# Senslope_Alpha_4_8.net
KiCad netlist of a schematic drawn in EAGLE
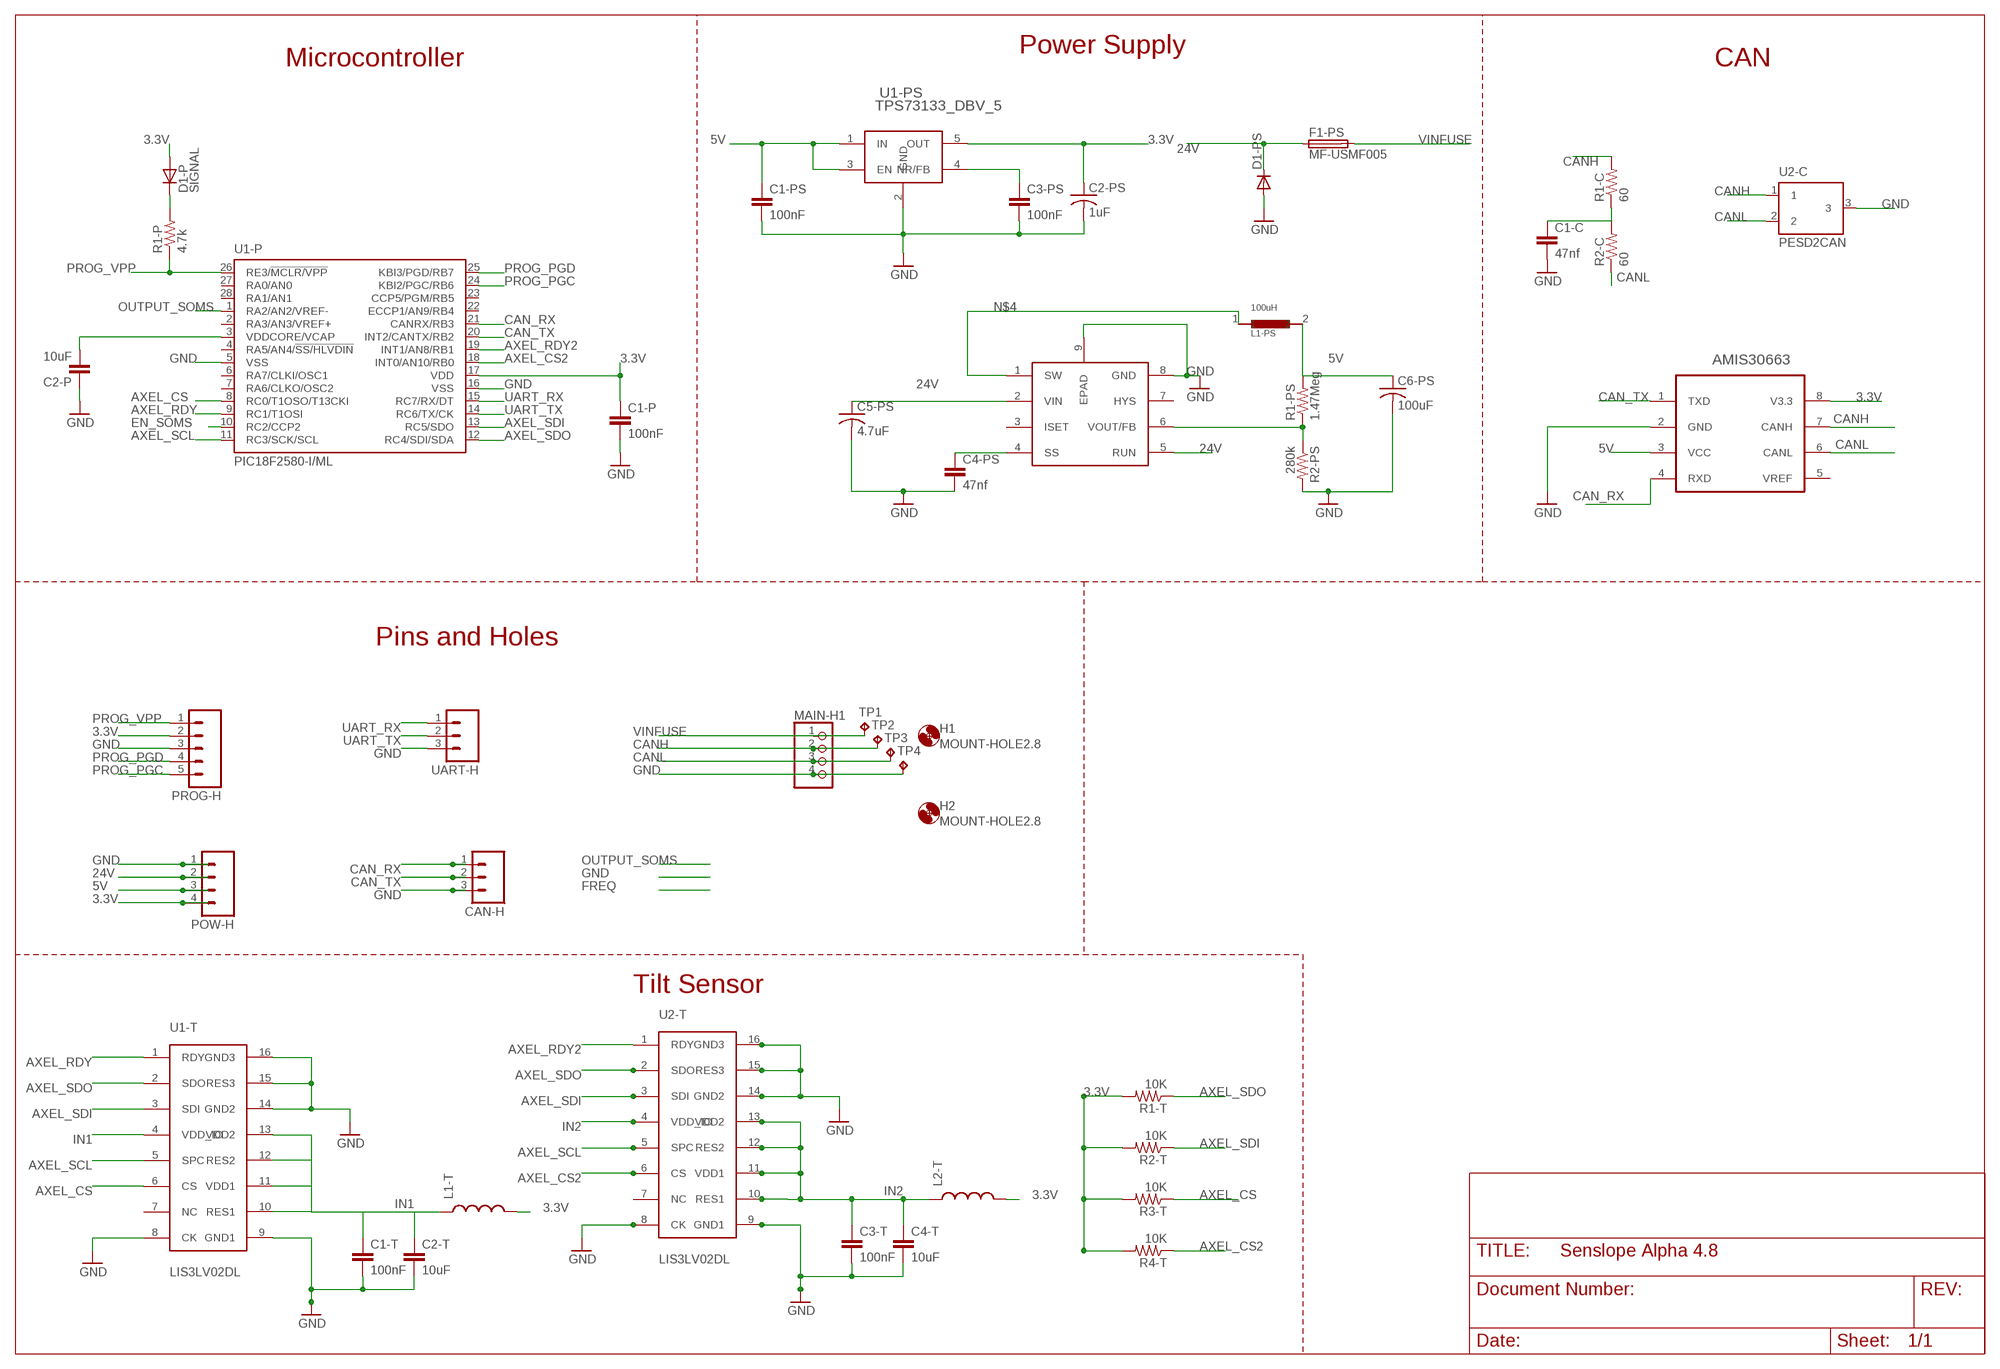
[diagram p0: schematic, sheet 1]

(export (version "E")
  (design (tool "Eeschema 10.0.6"))
  (components
    (comp (ref "C1-C")
      (value "47nf")
      (footprint "eagle-import:C0805")
      (libsource (lib "eagle-import") (part "C-EUC0805"))
    )
    (comp (ref "C1-P")
      (value "100nF")
      (footprint "eagle-import:C0603")
      (libsource (lib "eagle-import") (part "resistor_C-EUC0603"))
    )
    (comp (ref "C1-PS")
      (value "100nF")
      (footprint "eagle-import:C0603")
      (libsource (lib "eagle-import") (part "C-EUC0603"))
    )
    (comp (ref "C1-T")
      (value "100nF")
      (footprint "eagle-import:C0402")
      (libsource (lib "eagle-import") (part "C-EUC0402"))
    )
    (comp (ref "C2-P")
      (value "10uF")
      (footprint "eagle-import:C0603")
      (libsource (lib "eagle-import") (part "C-EUC0603"))
    )
    (comp (ref "C2-PS")
      (value "1uF")
      (footprint "eagle-import:C0402")
      (libsource (lib "eagle-import") (part "C-USC0402"))
    )
    (comp (ref "C2-T")
      (value "10uF")
      (footprint "eagle-import:C0402")
      (libsource (lib "eagle-import") (part "C-EUC0402"))
    )
    (comp (ref "C3-PS")
      (value "100nF")
      (footprint "eagle-import:C0603")
      (libsource (lib "eagle-import") (part "C-EUC0603"))
    )
    (comp (ref "C3-T")
      (value "100nF")
      (footprint "eagle-import:C0402")
      (libsource (lib "eagle-import") (part "C-EUC0402"))
    )
    (comp (ref "C4-PS")
      (value "47nf")
      (footprint "eagle-import:C0805")
      (libsource (lib "eagle-import") (part "C-EUC0805"))
    )
    (comp (ref "C4-T")
      (value "10uF")
      (footprint "eagle-import:C0402")
      (libsource (lib "eagle-import") (part "C-EUC0402"))
    )
    (comp (ref "C5-PS")
      (value "4.7uF")
      (footprint "eagle-import:C1206K")
      (libsource (lib "eagle-import") (part "C-USC1206K"))
    )
    (comp (ref "C6-PS")
      (value "100uF")
      (footprint "eagle-import:C1210K")
      (libsource (lib "eagle-import") (part "C-USC1210K"))
    )
    (comp (ref "CAN-H")
      (value "UART")
      (footprint "eagle-import:1X03_NO_SILK")
      (libsource (lib "eagle-import") (part "M031X03_NO_SILK"))
    )
    (comp (ref "D1-P")
      (value "SIGNAL")
      (footprint "eagle-import:DIODE-0603")
      (libsource (lib "eagle-import") (part "DIODE0603"))
    )
    (comp (ref "D1-PS")
      (value "DIODE-DO-214AC")
      (footprint "eagle-import:DO-214AC")
      (libsource (lib "eagle-import") (part "DIODE-DO-214AC"))
    )
    (comp (ref "F1-PS")
      (value "MF-USMF005")
      (footprint "eagle-import:1210")
      (libsource (lib "eagle-import") (part "MF-USMF075"))
    )
    (comp (ref "H1")
      (value "MOUNT-HOLE2.8")
      (footprint "eagle-import:2,8")
      (libsource (lib "eagle-import") (part "MOUNT-HOLE2.8"))
    )
    (comp (ref "H2")
      (value "MOUNT-HOLE2.8")
      (footprint "eagle-import:2,8")
      (libsource (lib "eagle-import") (part "MOUNT-HOLE2.8"))
    )
    (comp (ref "L1-PS")
      (value "100uH")
      (footprint "eagle-import:1210")
      (libsource (lib "eagle-import") (part "LQH32PN101MN0L"))
    )
    (comp (ref "L1-T")
      (value "H2")
      (footprint "eagle-import:C0402")
      (libsource (lib "eagle-import") (part "INDUCTOR0402"))
    )
    (comp (ref "L2-T")
      (value "H1")
      (footprint "eagle-import:C0402")
      (libsource (lib "eagle-import") (part "INDUCTOR0402"))
    )
    (comp (ref "MAIN-H1")
      (value "PINHD-1X04_2.54")
      (footprint "eagle-import:1X04")
      (libsource (lib "eagle-import") (part "PINHD-1X04_2.54"))
    )
    (comp (ref "POW-H")
      (value "M041X04_NO_SILK")
      (footprint "eagle-import:1X04_NO_SILK")
      (libsource (lib "eagle-import") (part "M041X04_NO_SILK"))
    )
    (comp (ref "PROG-H")
      (value "M05PTH")
      (footprint "eagle-import:1X05")
      (libsource (lib "eagle-import") (part "M05PTH"))
    )
    (comp (ref "R1-C")
      (value "60")
      (footprint "eagle-import:R0805")
      (libsource (lib "eagle-import") (part "R-US_R0805"))
    )
    (comp (ref "R1-P")
      (value "4.7k")
      (footprint "eagle-import:R0603")
      (libsource (lib "eagle-import") (part "resistor_R-US_R0603"))
    )
    (comp (ref "R1-PS")
      (value "1.47Meg")
      (footprint "eagle-import:R0805")
      (libsource (lib "eagle-import") (part "R-US_R0805"))
    )
    (comp (ref "R1-T")
      (value "10K")
      (footprint "eagle-import:R0603")
      (libsource (lib "eagle-import") (part "resistor_R-US_R0603"))
    )
    (comp (ref "R2-C")
      (value "60")
      (footprint "eagle-import:R0805")
      (libsource (lib "eagle-import") (part "R-US_R0805"))
    )
    (comp (ref "R2-PS")
      (value "280k")
      (footprint "eagle-import:R0805")
      (libsource (lib "eagle-import") (part "R-US_R0805"))
    )
    (comp (ref "R2-T")
      (value "10K")
      (footprint "eagle-import:R0603")
      (libsource (lib "eagle-import") (part "resistor_R-US_R0603"))
    )
    (comp (ref "R3-T")
      (value "10K")
      (footprint "eagle-import:R0603")
      (libsource (lib "eagle-import") (part "resistor_R-US_R0603"))
    )
    (comp (ref "R4-T")
      (value "10K")
      (footprint "eagle-import:R0603")
      (libsource (lib "eagle-import") (part "resistor_R-US_R0603"))
    )
    (comp (ref "TP1")
      (value "TPTP10SQ")
      (footprint "eagle-import:TP10SQ")
      (libsource (lib "eagle-import") (part "TPTP10SQ"))
    )
    (comp (ref "TP2")
      (value "TPTP10SQ")
      (footprint "eagle-import:TP10SQ")
      (libsource (lib "eagle-import") (part "TPTP10SQ"))
    )
    (comp (ref "TP3")
      (value "TPTP10SQ")
      (footprint "eagle-import:TP10SQ")
      (libsource (lib "eagle-import") (part "TPTP10SQ"))
    )
    (comp (ref "TP4")
      (value "TPTP10SQ")
      (footprint "eagle-import:TP10SQ")
      (libsource (lib "eagle-import") (part "TPTP10SQ"))
    )
    (comp (ref "U1-P")
      (value "PIC18F2580-I/ML")
      (footprint "eagle-import:QFN28-ML_6X6MM")
      (fields (field (name "MF") "MICROCHIP"))
      (libsource (lib "eagle-import") (part "PIC18F280-I/ML5"))
    )
    (comp (ref "U1-PS")
      (value "TPS73133_DBV_5")
      (footprint "eagle-import:DBV5")
      (fields
        (field (name "GENERIC_PART_NUMBER") "TPS73133")
        (field (name "MANUFACTURER") "Texas Instruments")
        (field (name "MANUFACTURER_PART_NUMBER") "tps73133_dbv_5")
      )
      (libsource (lib "eagle-import") (part "TPS73133_DBV_5"))
    )
    (comp (ref "U1-T")
      (value "LIS3LV02DL")
      (footprint "eagle-import:LGA16")
      (libsource (lib "eagle-import") (part "LIS3LV02DL"))
    )
    (comp (ref "U2")
      (value "AMIS30663CAN")
      (footprint "eagle-import:SOIC8")
      (fields (field (name "MPN") "AMIS30663"))
      (libsource (lib "eagle-import") (part "AMIS30663CAN"))
    )
    (comp (ref "U2-C")
      (value "PESD2CAN")
      (footprint "eagle-import:SOT23")
      (libsource (lib "eagle-import") (part "PESD2CAN"))
    )
    (comp (ref "U2-PS")
      (value "LTC3631-5")
      (footprint "eagle-import:MSOP8E")
      (libsource (lib "eagle-import") (part "LTC3631"))
    )
    (comp (ref "U2-T")
      (value "LIS3LV02DL")
      (footprint "eagle-import:LGA16")
      (libsource (lib "eagle-import") (part "LIS3LV02DL"))
    )
    (comp (ref "UART-H")
      (value "UART")
      (footprint "eagle-import:1X03_NO_SILK")
      (libsource (lib "eagle-import") (part "M031X03_NO_SILK"))
    )
  )
  (nets
    (net (code "1") (name "/3.3V") (class "Default")
      (node (ref "C1-P") (pin "1") (pinfunction "1_1") (pintype "passive"))
      (node (ref "C2-PS") (pin "1") (pinfunction "1_1") (pintype "passive"))
      (node (ref "D1-P") (pin "A") (pinfunction "A_A") (pintype "passive"))
      (node (ref "L1-T") (pin "2") (pinfunction "2_2") (pintype "passive"))
      (node (ref "L2-T") (pin "2") (pinfunction "2_2") (pintype "passive"))
      (node (ref "POW-H") (pin "4") (pinfunction "4_4") (pintype "passive"))
      (node (ref "PROG-H") (pin "2") (pinfunction "2_2") (pintype "passive"))
      (node (ref "R1-T") (pin "2") (pinfunction "2_2") (pintype "passive"))
      (node (ref "R2-T") (pin "2") (pinfunction "2_2") (pintype "passive"))
      (node (ref "R3-T") (pin "2") (pinfunction "2_2") (pintype "passive"))
      (node (ref "R4-T") (pin "2") (pinfunction "2_2") (pintype "passive"))
      (node (ref "U1-P") (pin "17") (pinfunction "VDD_17") (pintype "power_in"))
      (node (ref "U1-PS") (pin "5") (pinfunction "OUT_5") (pintype "output"))
      (node (ref "U2") (pin "8") (pinfunction "V3.3_8") (pintype "bidirectional"))
    )
    (net (code "2") (name "/5V") (class "Default")
      (node (ref "C1-PS") (pin "1") (pinfunction "1_1") (pintype "passive"))
      (node (ref "C6-PS") (pin "1") (pinfunction "1_1") (pintype "passive"))
      (node (ref "L1-PS") (pin "2") (pinfunction "2_2") (pintype "bidirectional"))
      (node (ref "POW-H") (pin "3") (pinfunction "3_3") (pintype "passive"))
      (node (ref "R1-PS") (pin "2") (pinfunction "2_2") (pintype "passive"))
      (node (ref "U1-PS") (pin "1") (pinfunction "IN_1") (pintype "input"))
      (node (ref "U1-PS") (pin "3") (pinfunction "EN_3") (pintype "passive"))
      (node (ref "U2") (pin "3") (pinfunction "VCC_3") (pintype "bidirectional"))
    )
    (net (code "3") (name "/24V") (class "Default")
      (node (ref "C5-PS") (pin "1") (pinfunction "1_1") (pintype "passive"))
      (node (ref "D1-PS") (pin "1") (pinfunction "C_1") (pintype "passive"))
      (node (ref "F1-PS") (pin "1") (pinfunction "1_1") (pintype "passive"))
      (node (ref "POW-H") (pin "2") (pinfunction "2_2") (pintype "passive"))
      (node (ref "U2-PS") (pin "2") (pinfunction "VIN_2") (pintype "bidirectional"))
      (node (ref "U2-PS") (pin "5") (pinfunction "RUN_5") (pintype "bidirectional"))
    )
    (net (code "4") (name "/AXEL_CS") (class "Default")
      (node (ref "R3-T") (pin "1") (pinfunction "1_1") (pintype "passive"))
      (node (ref "U1-P") (pin "8") (pinfunction "RC0/T1OSO/T13CKI_8") (pintype "bidirectional"))
      (node (ref "U1-T") (pin "6") (pinfunction "CS_6") (pintype "bidirectional"))
    )
    (net (code "5") (name "/AXEL_CS2") (class "Default")
      (node (ref "R4-T") (pin "1") (pinfunction "1_1") (pintype "passive"))
      (node (ref "U1-P") (pin "18") (pinfunction "INT0/AN10/RB0_18") (pintype "bidirectional"))
      (node (ref "U2-T") (pin "6") (pinfunction "CS_6") (pintype "bidirectional"))
    )
    (net (code "6") (name "/AXEL_RDY") (class "Default")
      (node (ref "U1-P") (pin "9") (pinfunction "RC1/T1OSI_9") (pintype "bidirectional"))
      (node (ref "U1-T") (pin "1") (pinfunction "RDY_1") (pintype "bidirectional"))
    )
    (net (code "7") (name "/AXEL_RDY2") (class "Default")
      (node (ref "U1-P") (pin "19") (pinfunction "INT1/AN8/RB1_19") (pintype "bidirectional"))
      (node (ref "U2-T") (pin "1") (pinfunction "RDY_1") (pintype "bidirectional"))
    )
    (net (code "8") (name "/AXEL_SCL") (class "Default")
      (node (ref "U1-P") (pin "11") (pinfunction "RC3/SCK/SCL_11") (pintype "bidirectional"))
      (node (ref "U1-T") (pin "5") (pinfunction "SPC_5") (pintype "bidirectional"))
      (node (ref "U2-T") (pin "5") (pinfunction "SPC_5") (pintype "bidirectional"))
    )
    (net (code "9") (name "/AXEL_SDI") (class "Default")
      (node (ref "R2-T") (pin "1") (pinfunction "1_1") (pintype "passive"))
      (node (ref "U1-P") (pin "13") (pinfunction "RC5/SDO_13") (pintype "bidirectional"))
      (node (ref "U1-T") (pin "3") (pinfunction "SDI_3") (pintype "bidirectional"))
      (node (ref "U2-T") (pin "3") (pinfunction "SDI_3") (pintype "bidirectional"))
    )
    (net (code "10") (name "/AXEL_SDO") (class "Default")
      (node (ref "R1-T") (pin "1") (pinfunction "1_1") (pintype "passive"))
      (node (ref "U1-P") (pin "12") (pinfunction "RC4/SDI/SDA_12") (pintype "bidirectional"))
      (node (ref "U1-T") (pin "2") (pinfunction "SDO_2") (pintype "bidirectional"))
      (node (ref "U2-T") (pin "2") (pinfunction "SDO_2") (pintype "bidirectional"))
    )
    (net (code "11") (name "/CANH") (class "Default")
      (node (ref "MAIN-H1") (pin "2") (pinfunction "2_2") (pintype "passive"))
      (node (ref "R1-C") (pin "2") (pinfunction "2_2") (pintype "passive"))
      (node (ref "TP2") (pin "TP") (pinfunction "TP_TP") (pintype "input"))
      (node (ref "U2") (pin "7") (pinfunction "CANH_7") (pintype "bidirectional"))
      (node (ref "U2-C") (pin "1") (pinfunction "1_1") (pintype "input"))
    )
    (net (code "12") (name "/CANL") (class "Default")
      (node (ref "MAIN-H1") (pin "3") (pinfunction "3_3") (pintype "passive"))
      (node (ref "R2-C") (pin "1") (pinfunction "1_1") (pintype "passive"))
      (node (ref "TP3") (pin "TP") (pinfunction "TP_TP") (pintype "input"))
      (node (ref "U2") (pin "6") (pinfunction "CANL_6") (pintype "bidirectional"))
      (node (ref "U2-C") (pin "2") (pinfunction "2_2") (pintype "power_in"))
    )
    (net (code "13") (name "/CAN_RX") (class "Default")
      (node (ref "CAN-H") (pin "1") (pinfunction "1_1") (pintype "passive"))
      (node (ref "U1-P") (pin "21") (pinfunction "CANRX/RB3_21") (pintype "bidirectional"))
      (node (ref "U2") (pin "4") (pinfunction "RXD_4") (pintype "bidirectional"))
    )
    (net (code "14") (name "/CAN_TX") (class "Default")
      (node (ref "CAN-H") (pin "2") (pinfunction "2_2") (pintype "passive"))
      (node (ref "U1-P") (pin "20") (pinfunction "INT2/CANTX/RB2_20") (pintype "bidirectional"))
      (node (ref "U2") (pin "1") (pinfunction "TXD_1") (pintype "bidirectional"))
    )
    (net (code "15") (name "/EN_SOMS") (class "Default")
      (node (ref "U1-P") (pin "10") (pinfunction "RC2/CCP2_10") (pintype "bidirectional"))
    )
    (net (code "17") (name "/IN1") (class "Default")
      (node (ref "C1-T") (pin "1") (pinfunction "1_1") (pintype "passive"))
      (node (ref "C2-T") (pin "1") (pinfunction "1_1") (pintype "passive"))
      (node (ref "L1-T") (pin "1") (pinfunction "1_1") (pintype "passive"))
      (node (ref "U1-T") (pin "10") (pinfunction "RES1_10") (pintype "bidirectional"))
      (node (ref "U1-T") (pin "11") (pinfunction "VDD1_11") (pintype "bidirectional"))
      (node (ref "U1-T") (pin "12") (pinfunction "RES2_12") (pintype "bidirectional"))
      (node (ref "U1-T") (pin "13") (pinfunction "VDD2_13") (pintype "bidirectional"))
      (node (ref "U1-T") (pin "4") (pinfunction "VDD_IO_4") (pintype "bidirectional"))
    )
    (net (code "18") (name "/IN2") (class "Default")
      (node (ref "C3-T") (pin "1") (pinfunction "1_1") (pintype "passive"))
      (node (ref "C4-T") (pin "1") (pinfunction "1_1") (pintype "passive"))
      (node (ref "L2-T") (pin "1") (pinfunction "1_1") (pintype "passive"))
      (node (ref "U2-T") (pin "10") (pinfunction "RES1_10") (pintype "bidirectional"))
      (node (ref "U2-T") (pin "11") (pinfunction "VDD1_11") (pintype "bidirectional"))
      (node (ref "U2-T") (pin "12") (pinfunction "RES2_12") (pintype "bidirectional"))
      (node (ref "U2-T") (pin "13") (pinfunction "VDD2_13") (pintype "bidirectional"))
      (node (ref "U2-T") (pin "4") (pinfunction "VDD_IO_4") (pintype "bidirectional"))
    )
    (net (code "19") (name "/N$4") (class "Default")
      (node (ref "L1-PS") (pin "1") (pinfunction "1_1") (pintype "bidirectional"))
      (node (ref "U2-PS") (pin "1") (pinfunction "SW_1") (pintype "bidirectional"))
    )
    (net (code "20") (name "/OUTPUT_SOMS") (class "Default")
      (node (ref "U1-P") (pin "1") (pinfunction "RA2/AN2/VREF-_1") (pintype "bidirectional"))
    )
    (net (code "21") (name "/PROG_PGC") (class "Default")
      (node (ref "PROG-H") (pin "5") (pinfunction "5_5") (pintype "passive"))
      (node (ref "U1-P") (pin "24") (pinfunction "KBI2/PGC/RB6_24") (pintype "bidirectional"))
    )
    (net (code "22") (name "/PROG_PGD") (class "Default")
      (node (ref "PROG-H") (pin "4") (pinfunction "4_4") (pintype "passive"))
      (node (ref "U1-P") (pin "25") (pinfunction "KBI3/PGD/RB7_25") (pintype "bidirectional"))
    )
    (net (code "23") (name "/PROG_VPP") (class "Default")
      (node (ref "PROG-H") (pin "1") (pinfunction "1_1") (pintype "passive"))
      (node (ref "R1-P") (pin "1") (pinfunction "1_1") (pintype "passive"))
      (node (ref "U1-P") (pin "26") (pinfunction "RE3/~{MCLR/VPP}_26") (pintype "input"))
    )
    (net (code "24") (name "/UART_RX") (class "Default")
      (node (ref "U1-P") (pin "15") (pinfunction "RC7/RX/DT_15") (pintype "bidirectional"))
      (node (ref "UART-H") (pin "1") (pinfunction "1_1") (pintype "passive"))
    )
    (net (code "25") (name "/UART_TX") (class "Default")
      (node (ref "U1-P") (pin "14") (pinfunction "RC6/TX/CK_14") (pintype "bidirectional"))
      (node (ref "UART-H") (pin "2") (pinfunction "2_2") (pintype "passive"))
    )
    (net (code "26") (name "/VINFUSE") (class "Default")
      (node (ref "F1-PS") (pin "2") (pinfunction "2_2") (pintype "passive"))
      (node (ref "MAIN-H1") (pin "1") (pinfunction "1_1") (pintype "passive"))
      (node (ref "TP1") (pin "TP") (pinfunction "TP_TP") (pintype "input"))
    )
    (net (code "27") (name "GND") (class "Default")
      (node (ref "C1-C") (pin "2") (pinfunction "2_2") (pintype "passive"))
      (node (ref "C1-P") (pin "2") (pinfunction "2_2") (pintype "passive"))
      (node (ref "C1-PS") (pin "2") (pinfunction "2_2") (pintype "passive"))
      (node (ref "C1-T") (pin "2") (pinfunction "2_2") (pintype "passive"))
      (node (ref "C2-P") (pin "1") (pinfunction "1_1") (pintype "passive"))
      (node (ref "C2-PS") (pin "2") (pinfunction "2_2") (pintype "passive"))
      (node (ref "C2-T") (pin "2") (pinfunction "2_2") (pintype "passive"))
      (node (ref "C3-PS") (pin "2") (pinfunction "2_2") (pintype "passive"))
      (node (ref "C3-T") (pin "2") (pinfunction "2_2") (pintype "passive"))
      (node (ref "C4-PS") (pin "2") (pinfunction "2_2") (pintype "passive"))
      (node (ref "C4-T") (pin "2") (pinfunction "2_2") (pintype "passive"))
      (node (ref "C5-PS") (pin "2") (pinfunction "2_2") (pintype "passive"))
      (node (ref "C6-PS") (pin "2") (pinfunction "2_2") (pintype "passive"))
      (node (ref "CAN-H") (pin "3") (pinfunction "3_3") (pintype "passive"))
      (node (ref "D1-PS") (pin "2") (pinfunction "A_2") (pintype "passive"))
      (node (ref "MAIN-H1") (pin "4") (pinfunction "4_4") (pintype "passive"))
      (node (ref "POW-H") (pin "1") (pinfunction "1_1") (pintype "passive"))
      (node (ref "PROG-H") (pin "3") (pinfunction "3_3") (pintype "passive"))
      (node (ref "R2-PS") (pin "2") (pinfunction "2_2") (pintype "passive"))
      (node (ref "TP4") (pin "TP") (pinfunction "TP_TP") (pintype "input"))
      (node (ref "U1-P") (pin "16") (pinfunction "VSS_16") (pintype "power_in"))
      (node (ref "U1-P") (pin "5") (pinfunction "VSS_5") (pintype "power_in"))
      (node (ref "U1-PS") (pin "2") (pinfunction "GND_2") (pintype "power_in"))
      (node (ref "U1-T") (pin "14") (pinfunction "GND2_14") (pintype "bidirectional"))
      (node (ref "U1-T") (pin "15") (pinfunction "RES3_15") (pintype "bidirectional"))
      (node (ref "U1-T") (pin "16") (pinfunction "GND3_16") (pintype "bidirectional"))
      (node (ref "U1-T") (pin "8") (pinfunction "CK_8") (pintype "bidirectional"))
      (node (ref "U1-T") (pin "9") (pinfunction "GND1_9") (pintype "bidirectional"))
      (node (ref "U2") (pin "2") (pinfunction "GND_2") (pintype "bidirectional"))
      (node (ref "U2-C") (pin "3") (pinfunction "3_3") (pintype "output"))
      (node (ref "U2-PS") (pin "8") (pinfunction "GND_8") (pintype "bidirectional"))
      (node (ref "U2-PS") (pin "9") (pinfunction "EPAD_9") (pintype "bidirectional"))
      (node (ref "U2-T") (pin "14") (pinfunction "GND2_14") (pintype "bidirectional"))
      (node (ref "U2-T") (pin "15") (pinfunction "RES3_15") (pintype "bidirectional"))
      (node (ref "U2-T") (pin "16") (pinfunction "GND3_16") (pintype "bidirectional"))
      (node (ref "U2-T") (pin "8") (pinfunction "CK_8") (pintype "bidirectional"))
      (node (ref "U2-T") (pin "9") (pinfunction "GND1_9") (pintype "bidirectional"))
      (node (ref "UART-H") (pin "3") (pinfunction "3_3") (pintype "passive"))
    )
    (net (code "28") (name "Net-(C1-C-Pad1)") (class "Default")
      (node (ref "C1-C") (pin "1") (pinfunction "1_1") (pintype "passive"))
      (node (ref "R1-C") (pin "1") (pinfunction "1_1") (pintype "passive"))
      (node (ref "R2-C") (pin "2") (pinfunction "2_2") (pintype "passive"))
    )
    (net (code "29") (name "Net-(D1-P-PadC)") (class "Default")
      (node (ref "D1-P") (pin "C") (pinfunction "C_C") (pintype "passive"))
      (node (ref "R1-P") (pin "2") (pinfunction "2_2") (pintype "passive"))
    )
    (net (code "30") (name "Net-(U1-P-VDDCORE{slash}VCAP)") (class "Default")
      (node (ref "C2-P") (pin "2") (pinfunction "2_2") (pintype "passive"))
      (node (ref "U1-P") (pin "3") (pinfunction "VDDCORE/VCAP_3") (pintype "bidirectional"))
    )
    (net (code "31") (name "Net-(U1-PS-NR{slash}FB)") (class "Default")
      (node (ref "C3-PS") (pin "1") (pinfunction "1_1") (pintype "passive"))
      (node (ref "U1-PS") (pin "4") (pinfunction "NR/FB_4") (pintype "passive"))
    )
    (net (code "32") (name "Net-(U2-PS-SS)") (class "Default")
      (node (ref "C4-PS") (pin "1") (pinfunction "1_1") (pintype "passive"))
      (node (ref "U2-PS") (pin "4") (pinfunction "SS_4") (pintype "bidirectional"))
    )
    (net (code "33") (name "Net-(U2-PS-VOUT{slash}FB)") (class "Default")
      (node (ref "R1-PS") (pin "1") (pinfunction "1_1") (pintype "passive"))
      (node (ref "R2-PS") (pin "1") (pinfunction "1_1") (pintype "passive"))
      (node (ref "U2-PS") (pin "6") (pinfunction "VOUT/FB_6") (pintype "bidirectional"))
    )
    (net (code "34") (name "unconnected-(U1-P-CCP5{slash}PGM{slash}RB5-Pad23)") (class "Default")
      (node (ref "U1-P") (pin "23") (pinfunction "CCP5/PGM/RB5_23") (pintype "bidirectional"))
    )
    (net (code "35") (name "unconnected-(U1-P-ECCP1{slash}AN9{slash}RB4-Pad22)") (class "Default")
      (node (ref "U1-P") (pin "22") (pinfunction "ECCP1/AN9/RB4_22") (pintype "bidirectional"))
    )
    (net (code "36") (name "unconnected-(U1-P-RA0{slash}AN0-Pad27)") (class "Default")
      (node (ref "U1-P") (pin "27") (pinfunction "RA0/AN0_27") (pintype "bidirectional"))
    )
    (net (code "37") (name "unconnected-(U1-P-RA1{slash}AN1-Pad28)") (class "Default")
      (node (ref "U1-P") (pin "28") (pinfunction "RA1/AN1_28") (pintype "bidirectional"))
    )
    (net (code "38") (name "unconnected-(U1-P-RA3{slash}AN3{slash}VREF+-Pad2)") (class "Default")
      (node (ref "U1-P") (pin "2") (pinfunction "RA3/AN3/VREF+_2") (pintype "bidirectional"))
    )
    (net (code "39") (name "unconnected-(U1-P-RA5{slash}AN4{slash}~{SS{slash}HLVDIN}-Pad4)") (class "Default")
      (node (ref "U1-P") (pin "4") (pinfunction "RA5/AN4/~{SS/HLVDIN}_4") (pintype "bidirectional"))
    )
    (net (code "40") (name "unconnected-(U1-P-RA6{slash}CLKO{slash}OSC2-Pad7)") (class "Default")
      (node (ref "U1-P") (pin "7") (pinfunction "RA6/CLKO/OSC2_7") (pintype "output"))
    )
    (net (code "41") (name "unconnected-(U1-P-RA7{slash}CLKI{slash}OSC1-Pad6)") (class "Default")
      (node (ref "U1-P") (pin "6") (pinfunction "RA7/CLKI/OSC1_6") (pintype "input"))
    )
    (net (code "42") (name "unconnected-(U1-T-NC-Pad7)") (class "Default")
      (node (ref "U1-T") (pin "7") (pinfunction "NC_7") (pintype "bidirectional"))
    )
    (net (code "43") (name "unconnected-(U2-PS-HYS-Pad7)") (class "Default")
      (node (ref "U2-PS") (pin "7") (pinfunction "HYS_7") (pintype "bidirectional"))
    )
    (net (code "44") (name "unconnected-(U2-PS-ISET-Pad3)") (class "Default")
      (node (ref "U2-PS") (pin "3") (pinfunction "ISET_3") (pintype "bidirectional"))
    )
    (net (code "45") (name "unconnected-(U2-T-NC-Pad7)") (class "Default")
      (node (ref "U2-T") (pin "7") (pinfunction "NC_7") (pintype "bidirectional"))
    )
    (net (code "46") (name "unconnected-(U2-VREF-Pad5)") (class "Default")
      (node (ref "U2") (pin "5") (pinfunction "VREF_5") (pintype "bidirectional"))
    )
  )
)
